# HackBoard.net
KiCad netlist of a schematic drawn in EAGLE
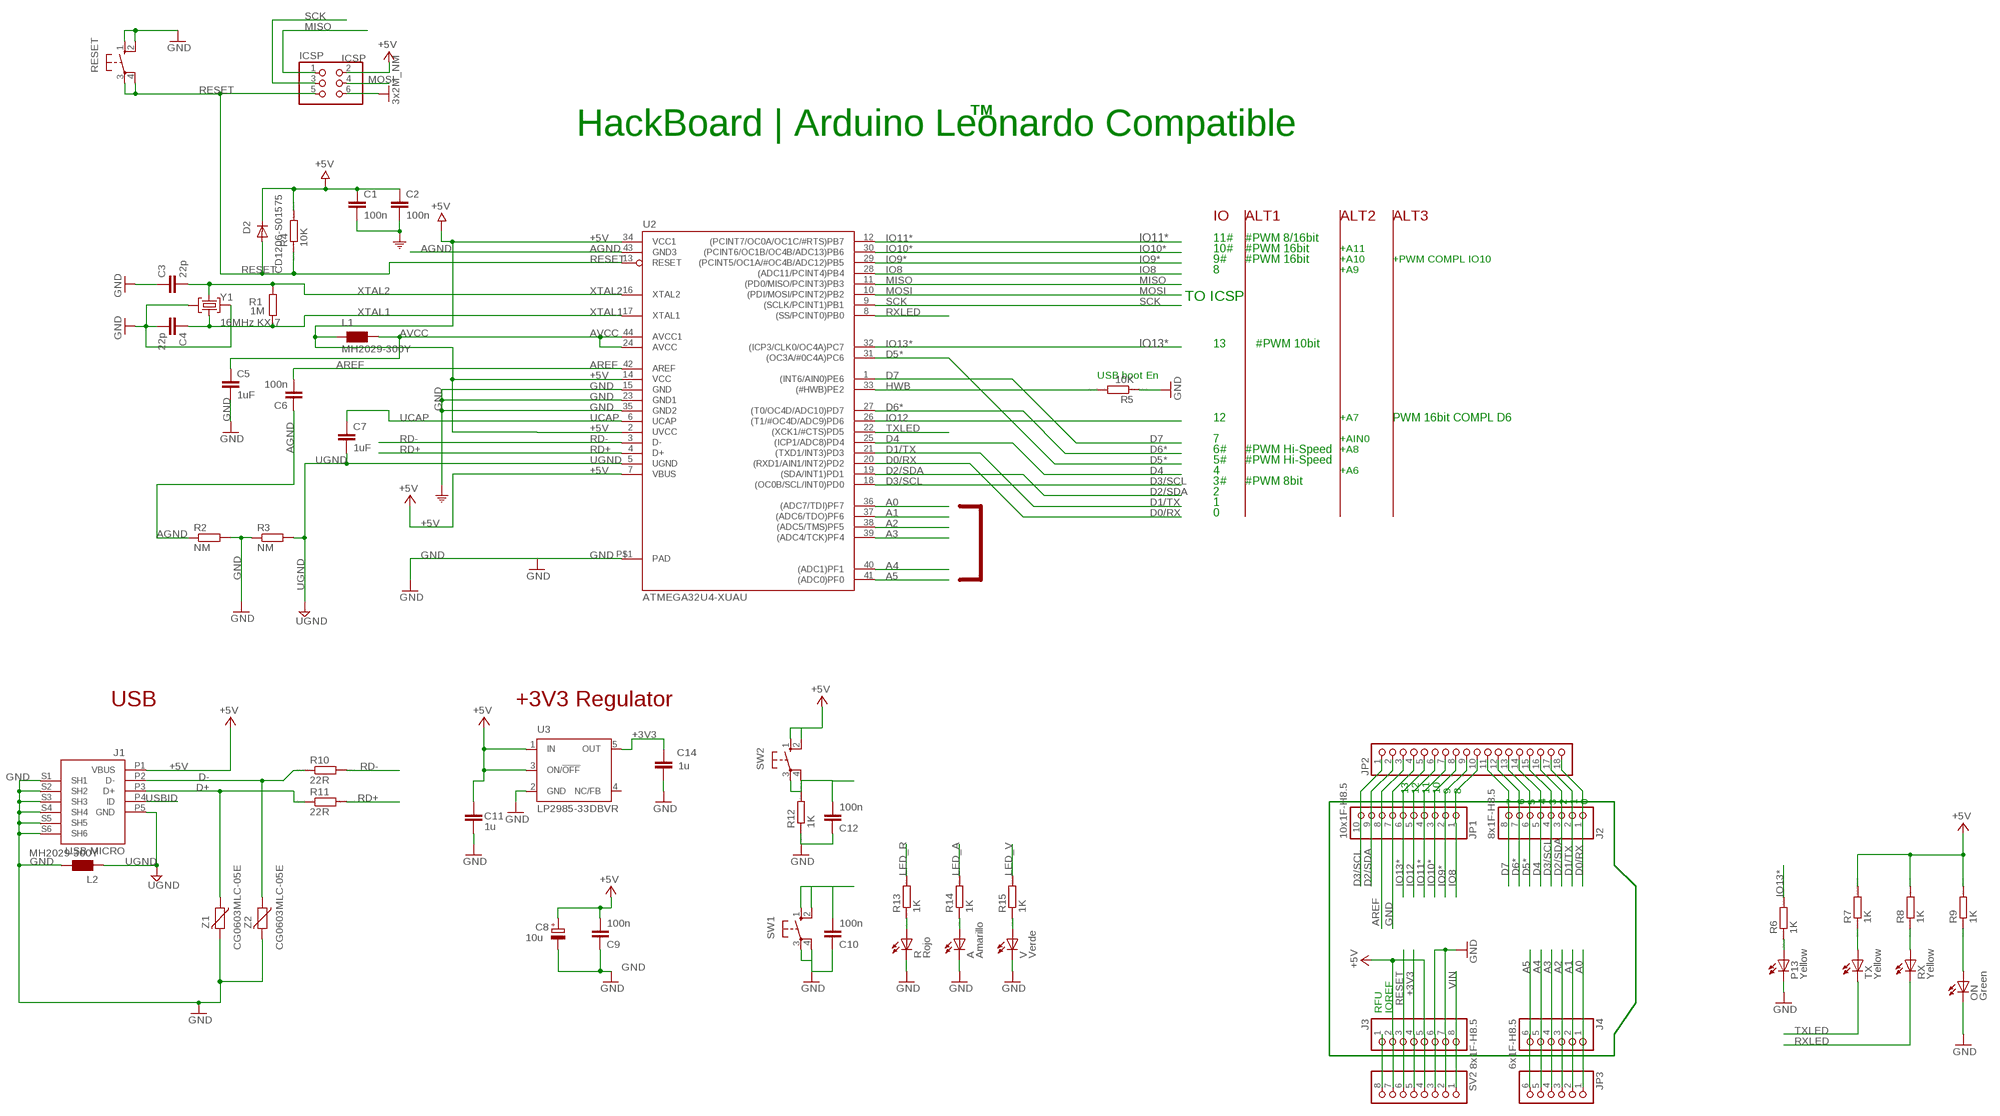
[diagram p0: schematic, sheet 1]

(export (version "E")
  (design (tool "Eeschema 10.0.6"))
  (components
    (comp (ref "A")
      (value "Amarillo")
      (footprint "eagle-import:CHIPLED_0805")
      (libsource (lib "eagle-import") (part "LEDCHIPLED_0805"))
    )
    (comp (ref "C1")
      (value "100n")
      (footprint "eagle-import:C0805")
      (libsource (lib "eagle-import") (part "rcl_C-EUC0805"))
    )
    (comp (ref "C2")
      (value "100n")
      (footprint "eagle-import:C0805")
      (libsource (lib "eagle-import") (part "rcl_C-EUC0805"))
    )
    (comp (ref "C3")
      (value "22p")
      (footprint "eagle-import:C0603-ROUND")
      (libsource (lib "eagle-import") (part "C-EUC0603"))
    )
    (comp (ref "C4")
      (value "22p")
      (footprint "eagle-import:C0603-ROUND")
      (libsource (lib "eagle-import") (part "C-EUC0603"))
    )
    (comp (ref "C5")
      (value "1uF")
      (footprint "eagle-import:C0603-ROUND")
      (libsource (lib "eagle-import") (part "C-EUC0603"))
    )
    (comp (ref "C6")
      (value "100n")
      (footprint "eagle-import:C0805")
      (libsource (lib "eagle-import") (part "rcl_C-EUC0805"))
    )
    (comp (ref "C7")
      (value "1uF")
      (footprint "eagle-import:C0603-ROUND")
      (libsource (lib "eagle-import") (part "C-EUC0603"))
    )
    (comp (ref "C8")
      (value "10u")
      (footprint "eagle-import:SMC_B")
      (libsource (lib "eagle-import") (part "CPOL-EUSMCB"))
    )
    (comp (ref "C9")
      (value "100n")
      (footprint "eagle-import:C0805")
      (libsource (lib "eagle-import") (part "rcl_C-EUC0805"))
    )
    (comp (ref "C10")
      (value "100n")
      (footprint "eagle-import:C0805")
      (libsource (lib "eagle-import") (part "rcl_C-EUC0805"))
    )
    (comp (ref "C11")
      (value "1u")
      (footprint "eagle-import:C0603-ROUND")
      (libsource (lib "eagle-import") (part "C-EUC0603"))
    )
    (comp (ref "C12")
      (value "100n")
      (footprint "eagle-import:C0805")
      (libsource (lib "eagle-import") (part "rcl_C-EUC0805"))
    )
    (comp (ref "C14")
      (value "1u")
      (footprint "eagle-import:C0603-ROUND")
      (libsource (lib "eagle-import") (part "C-EUC0603"))
    )
    (comp (ref "D2")
      (value "CD1206-S01575")
      (footprint "eagle-import:MINIMELF")
      (libsource (lib "eagle-import") (part "DIODE-MINIMELF"))
    )
    (comp (ref "ICSP")
      (value "ICSP")
      (footprint "eagle-import:2X03")
      (libsource (lib "eagle-import") (part "PINHD-2X3"))
    )
    (comp (ref "J1")
      (value "USB MICRO")
      (footprint "eagle-import:CON2_USB_MICRO_B_AT")
      (libsource (lib "eagle-import") (part "MYCON2_USB-MINI-B"))
    )
    (comp (ref "J2")
      (value "8x1F-H8.5")
      (footprint "eagle-import:1X08")
      (libsource (lib "eagle-import") (part "PINHD-1X8"))
    )
    (comp (ref "J3")
      (value "8x1F-H8.5")
      (footprint "eagle-import:1X08")
      (libsource (lib "eagle-import") (part "PINHD-1X8"))
    )
    (comp (ref "J4")
      (value "6x1F-H8.5")
      (footprint "eagle-import:1X06")
      (libsource (lib "eagle-import") (part "PINHD-1X6"))
    )
    (comp (ref "JP1")
      (value "10x1F-H8.5")
      (footprint "eagle-import:1X10")
      (libsource (lib "eagle-import") (part "PINHD-1X10"))
    )
    (comp (ref "JP2")
      (value "PINHD-1X18")
      (footprint "eagle-import:1X18")
      (libsource (lib "eagle-import") (part "PINHD-1X18"))
    )
    (comp (ref "JP3")
      (value "PINHD-1X6")
      (footprint "eagle-import:1X06")
      (libsource (lib "eagle-import") (part "pinhead_PINHD-1X6"))
    )
    (comp (ref "L1")
      (value "MH2029-300Y")
      (footprint "eagle-import:0805")
      (libsource (lib "eagle-import") (part "WE-CBF_0805"))
    )
    (comp (ref "L2")
      (value "MH2029-300Y")
      (footprint "eagle-import:0805")
      (libsource (lib "eagle-import") (part "WE-CBF_0805"))
    )
    (comp (ref "ON")
      (value "Green")
      (footprint "eagle-import:CHIPLED_0805")
      (libsource (lib "eagle-import") (part "LEDCHIPLED_0805"))
    )
    (comp (ref "P13")
      (value "Yellow")
      (footprint "eagle-import:CHIPLED_0805")
      (libsource (lib "eagle-import") (part "LEDCHIPLED_0805"))
    )
    (comp (ref "R")
      (value "Rojo")
      (footprint "eagle-import:CHIPLED_0805")
      (libsource (lib "eagle-import") (part "LEDCHIPLED_0805"))
    )
    (comp (ref "R1")
      (value "1M")
      (footprint "eagle-import:R0603-ROUND")
      (libsource (lib "eagle-import") (part "R-EU_R0603"))
    )
    (comp (ref "R2")
      (value "NM")
      (footprint "eagle-import:R0402")
      (libsource (lib "eagle-import") (part "R-EU_R0402"))
    )
    (comp (ref "R3")
      (value "NM")
      (footprint "eagle-import:R0402")
      (libsource (lib "eagle-import") (part "R-EU_R0402"))
    )
    (comp (ref "R4")
      (value "10K")
      (footprint "eagle-import:R0805")
      (libsource (lib "eagle-import") (part "R"))
    )
    (comp (ref "R5")
      (value "10K")
      (footprint "eagle-import:R0805")
      (libsource (lib "eagle-import") (part "R"))
    )
    (comp (ref "R6")
      (value "1K")
      (footprint "eagle-import:M0805")
      (libsource (lib "eagle-import") (part "resistor_R-EU_M0805"))
    )
    (comp (ref "R7")
      (value "1K")
      (footprint "eagle-import:M0805")
      (libsource (lib "eagle-import") (part "resistor_R-EU_M0805"))
    )
    (comp (ref "R8")
      (value "1K")
      (footprint "eagle-import:M0805")
      (libsource (lib "eagle-import") (part "resistor_R-EU_M0805"))
    )
    (comp (ref "R9")
      (value "1K")
      (footprint "eagle-import:M0805")
      (libsource (lib "eagle-import") (part "resistor_R-EU_M0805"))
    )
    (comp (ref "R10")
      (value "22R")
      (footprint "eagle-import:M0805")
      (libsource (lib "eagle-import") (part "resistor_R-EU_M0805"))
    )
    (comp (ref "R11")
      (value "22R")
      (footprint "eagle-import:M0805")
      (libsource (lib "eagle-import") (part "resistor_R-EU_M0805"))
    )
    (comp (ref "R12")
      (value "1K")
      (footprint "eagle-import:M0805")
      (libsource (lib "eagle-import") (part "resistor_R-EU_M0805"))
    )
    (comp (ref "R13")
      (value "1K")
      (footprint "eagle-import:M0805")
      (libsource (lib "eagle-import") (part "resistor_R-EU_M0805"))
    )
    (comp (ref "R14")
      (value "1K")
      (footprint "eagle-import:M0805")
      (libsource (lib "eagle-import") (part "resistor_R-EU_M0805"))
    )
    (comp (ref "R15")
      (value "1K")
      (footprint "eagle-import:M0805")
      (libsource (lib "eagle-import") (part "resistor_R-EU_M0805"))
    )
    (comp (ref "RESET")
      (value "10-XX")
      (footprint "eagle-import:B3F-10XX")
      (fields (field (name "MPN") "B3F-1000"))
      (libsource (lib "eagle-import") (part "10-XX"))
    )
    (comp (ref "RX")
      (value "Yellow")
      (footprint "eagle-import:CHIPLED_0805")
      (libsource (lib "eagle-import") (part "LEDCHIPLED_0805"))
    )
    (comp (ref "SV2")
      (value "PINHD-1X8")
      (footprint "eagle-import:1X08")
      (libsource (lib "eagle-import") (part "pinhead_PINHD-1X8"))
    )
    (comp (ref "SW1")
      (value "10-XX")
      (footprint "eagle-import:B3F-10XX")
      (fields (field (name "MPN") "B3F-1000"))
      (libsource (lib "eagle-import") (part "10-XX"))
    )
    (comp (ref "SW2")
      (value "10-XX")
      (footprint "eagle-import:B3F-10XX")
      (fields (field (name "MPN") "B3F-1000"))
      (libsource (lib "eagle-import") (part "10-XX"))
    )
    (comp (ref "TX")
      (value "Yellow")
      (footprint "eagle-import:CHIPLED_0805")
      (libsource (lib "eagle-import") (part "LEDCHIPLED_0805"))
    )
    (comp (ref "U2")
      (value "ATMEGA32U4-XUAU")
      (footprint "eagle-import:TQFP44-PAD")
      (libsource (lib "eagle-import") (part "ATMEGA32U4-XUAU"))
    )
    (comp (ref "U3")
      (value "LP2985-33DBVR")
      (footprint "eagle-import:SOT23-DBV")
      (libsource (lib "eagle-import") (part "LP2985-XXDBVR33"))
    )
    (comp (ref "V")
      (value "Verde")
      (footprint "eagle-import:CHIPLED_0805")
      (libsource (lib "eagle-import") (part "LEDCHIPLED_0805"))
    )
    (comp (ref "Y1")
      (value "16MHz KX-7")
      (footprint "eagle-import:CRYSTAL-3.2-2.5")
      (libsource (lib "eagle-import") (part "CRYSTAL-3.2-2.5"))
    )
    (comp (ref "Z1")
      (value "CG0603MLC-05E")
      (footprint "eagle-import:CT_CN0603")
      (libsource (lib "eagle-import") (part "VARISTORCN0603"))
    )
    (comp (ref "Z2")
      (value "CG0603MLC-05E")
      (footprint "eagle-import:CT_CN0603")
      (libsource (lib "eagle-import") (part "VARISTORCN0603"))
    )
  )
  (nets
    (net (code "1") (name "+5V") (class "Default")
      (node (ref "C1") (pin "1") (pinfunction "1_1") (pintype "passive"))
      (node (ref "C11") (pin "2") (pinfunction "2_2") (pintype "passive"))
      (node (ref "C2") (pin "1") (pinfunction "1_1") (pintype "passive"))
      (node (ref "C8") (pin "+") (pinfunction "+_+") (pintype "passive"))
      (node (ref "C9") (pin "2") (pinfunction "2_2") (pintype "passive"))
      (node (ref "D2") (pin "C") (pinfunction "C_C") (pintype "passive"))
      (node (ref "ICSP") (pin "2") (pinfunction "2_2") (pintype "passive"))
      (node (ref "J1") (pin "P1") (pinfunction "VBUS_P1") (pintype "power_in"))
      (node (ref "J3") (pin "2") (pinfunction "2_2") (pintype "passive"))
      (node (ref "J3") (pin "5") (pinfunction "5_5") (pintype "passive"))
      (node (ref "L1") (pin "1") (pinfunction "1_1") (pintype "passive"))
      (node (ref "R4") (pin "2") (pinfunction "2_2") (pintype "passive"))
      (node (ref "R7") (pin "2") (pinfunction "2_2") (pintype "passive"))
      (node (ref "R8") (pin "2") (pinfunction "2_2") (pintype "passive"))
      (node (ref "R9") (pin "2") (pinfunction "2_2") (pintype "passive"))
      (node (ref "SV2") (pin "4") (pinfunction "4_4") (pintype "passive"))
      (node (ref "SV2") (pin "7") (pinfunction "7_7") (pintype "passive"))
      (node (ref "SW2") (pin "1") (pinfunction "S_1") (pintype "passive"))
      (node (ref "SW2") (pin "2") (pinfunction "S1_2") (pintype "passive"))
      (node (ref "U2") (pin "14") (pinfunction "VCC_14") (pintype "power_in"))
      (node (ref "U2") (pin "2") (pinfunction "UVCC_2") (pintype "power_in"))
      (node (ref "U2") (pin "34") (pinfunction "VCC1_34") (pintype "power_in"))
      (node (ref "U2") (pin "7") (pinfunction "VBUS_7") (pintype "input"))
      (node (ref "U3") (pin "1") (pinfunction "IN_1") (pintype "input"))
      (node (ref "U3") (pin "3") (pinfunction "ON/~{OFF}_3") (pintype "input"))
    )
    (net (code "2") (name "/+3V3") (class "Default")
      (node (ref "C14") (pin "2") (pinfunction "2_2") (pintype "passive"))
      (node (ref "J3") (pin "4") (pinfunction "4_4") (pintype "passive"))
      (node (ref "SV2") (pin "5") (pinfunction "5_5") (pintype "passive"))
      (node (ref "U3") (pin "5") (pinfunction "OUT_5") (pintype "passive"))
    )
    (net (code "3") (name "/A0") (class "Default")
      (node (ref "J4") (pin "1") (pinfunction "1_1") (pintype "passive"))
      (node (ref "JP3") (pin "1") (pinfunction "1_1") (pintype "passive"))
      (node (ref "U2") (pin "36") (pinfunction "(ADC7/TDI)PF7_36") (pintype "bidirectional"))
    )
    (net (code "4") (name "/A1") (class "Default")
      (node (ref "J4") (pin "2") (pinfunction "2_2") (pintype "passive"))
      (node (ref "JP3") (pin "2") (pinfunction "2_2") (pintype "passive"))
      (node (ref "U2") (pin "37") (pinfunction "(ADC6/TDO)PF6_37") (pintype "bidirectional"))
    )
    (net (code "5") (name "/A2") (class "Default")
      (node (ref "J4") (pin "3") (pinfunction "3_3") (pintype "passive"))
      (node (ref "JP3") (pin "3") (pinfunction "3_3") (pintype "passive"))
      (node (ref "U2") (pin "38") (pinfunction "(ADC5/TMS)PF5_38") (pintype "bidirectional"))
    )
    (net (code "6") (name "/A3") (class "Default")
      (node (ref "J4") (pin "4") (pinfunction "4_4") (pintype "passive"))
      (node (ref "JP3") (pin "4") (pinfunction "4_4") (pintype "passive"))
      (node (ref "U2") (pin "39") (pinfunction "(ADC4/TCK)PF4_39") (pintype "bidirectional"))
    )
    (net (code "7") (name "/A4") (class "Default")
      (node (ref "J4") (pin "5") (pinfunction "5_5") (pintype "passive"))
      (node (ref "JP3") (pin "5") (pinfunction "5_5") (pintype "passive"))
      (node (ref "U2") (pin "40") (pinfunction "(ADC1)PF1_40") (pintype "bidirectional"))
    )
    (net (code "8") (name "/A5") (class "Default")
      (node (ref "J4") (pin "6") (pinfunction "6_6") (pintype "passive"))
      (node (ref "JP3") (pin "6") (pinfunction "6_6") (pintype "passive"))
      (node (ref "U2") (pin "41") (pinfunction "(ADC0)PF0_41") (pintype "bidirectional"))
    )
    (net (code "9") (name "/AGND") (class "Default")
      (node (ref "C6") (pin "1") (pinfunction "1_1") (pintype "passive"))
      (node (ref "R2") (pin "1") (pinfunction "1_1") (pintype "passive"))
      (node (ref "U2") (pin "43") (pinfunction "GND3_43") (pintype "power_in"))
    )
    (net (code "10") (name "/AREF") (class "Default")
      (node (ref "C6") (pin "2") (pinfunction "2_2") (pintype "passive"))
      (node (ref "JP1") (pin "8") (pinfunction "8_8") (pintype "passive"))
      (node (ref "JP2") (pin "3") (pinfunction "3_3") (pintype "passive"))
      (node (ref "U2") (pin "42") (pinfunction "AREF_42") (pintype "power_in"))
    )
    (net (code "11") (name "/AVCC") (class "Default")
      (node (ref "C5") (pin "1") (pinfunction "1_1") (pintype "passive"))
      (node (ref "L1") (pin "2") (pinfunction "2_2") (pintype "passive"))
      (node (ref "U2") (pin "24") (pinfunction "AVCC_24") (pintype "power_in"))
      (node (ref "U2") (pin "44") (pinfunction "AVCC1_44") (pintype "power_in"))
    )
    (net (code "12") (name "/D+") (class "Default")
      (node (ref "J1") (pin "P3") (pinfunction "D+_P3") (pintype "bidirectional"))
      (node (ref "R11") (pin "1") (pinfunction "1_1") (pintype "passive"))
      (node (ref "Z1") (pin "1") (pinfunction "1_1") (pintype "passive"))
    )
    (net (code "13") (name "/D-") (class "Default")
      (node (ref "J1") (pin "P2") (pinfunction "D-_P2") (pintype "bidirectional"))
      (node (ref "R10") (pin "1") (pinfunction "1_1") (pintype "passive"))
      (node (ref "Z2") (pin "1") (pinfunction "1_1") (pintype "passive"))
    )
    (net (code "14") (name "/D0{slash}RX") (class "Default")
      (node (ref "J2") (pin "1") (pinfunction "1_1") (pintype "passive"))
      (node (ref "JP2") (pin "18") (pinfunction "18_18") (pintype "passive"))
      (node (ref "U2") (pin "20") (pinfunction "(RXD1/AIN1/INT2)PD2_20") (pintype "bidirectional"))
    )
    (net (code "15") (name "/D1{slash}TX") (class "Default")
      (node (ref "J2") (pin "2") (pinfunction "2_2") (pintype "passive"))
      (node (ref "JP2") (pin "17") (pinfunction "17_17") (pintype "passive"))
      (node (ref "U2") (pin "21") (pinfunction "(TXD1/INT3)PD3_21") (pintype "bidirectional"))
    )
    (net (code "16") (name "/D2{slash}SDA") (class "Default")
      (node (ref "J2") (pin "3") (pinfunction "3_3") (pintype "passive"))
      (node (ref "JP1") (pin "9") (pinfunction "9_9") (pintype "passive"))
      (node (ref "JP2") (pin "16") (pinfunction "16_16") (pintype "passive"))
      (node (ref "JP2") (pin "2") (pinfunction "2_2") (pintype "passive"))
      (node (ref "U2") (pin "19") (pinfunction "(SDA/INT1)PD1_19") (pintype "bidirectional"))
    )
    (net (code "17") (name "/D3{slash}SCL") (class "Default")
      (node (ref "J2") (pin "4") (pinfunction "4_4") (pintype "passive"))
      (node (ref "JP1") (pin "10") (pinfunction "10_10") (pintype "passive"))
      (node (ref "JP2") (pin "1") (pinfunction "1_1") (pintype "passive"))
      (node (ref "JP2") (pin "15") (pinfunction "15_15") (pintype "passive"))
      (node (ref "U2") (pin "18") (pinfunction "(OC0B/SCL/INT0)PD0_18") (pintype "bidirectional"))
    )
    (net (code "18") (name "/D4") (class "Default")
      (node (ref "J2") (pin "5") (pinfunction "5_5") (pintype "passive"))
      (node (ref "JP2") (pin "14") (pinfunction "14_14") (pintype "passive"))
      (node (ref "U2") (pin "25") (pinfunction "(ICP1/ADC8)PD4_25") (pintype "bidirectional"))
    )
    (net (code "19") (name "/D5*") (class "Default")
      (node (ref "J2") (pin "6") (pinfunction "6_6") (pintype "passive"))
      (node (ref "JP2") (pin "13") (pinfunction "13_13") (pintype "passive"))
      (node (ref "U2") (pin "31") (pinfunction "(OC3A/#0C4A)PC6_31") (pintype "bidirectional"))
    )
    (net (code "20") (name "/D6*") (class "Default")
      (node (ref "J2") (pin "7") (pinfunction "7_7") (pintype "passive"))
      (node (ref "JP2") (pin "12") (pinfunction "12_12") (pintype "passive"))
      (node (ref "U2") (pin "27") (pinfunction "(T0/OC4D/ADC10)PD7_27") (pintype "bidirectional"))
    )
    (net (code "21") (name "/D7") (class "Default")
      (node (ref "J2") (pin "8") (pinfunction "8_8") (pintype "passive"))
      (node (ref "JP2") (pin "11") (pinfunction "11_11") (pintype "passive"))
      (node (ref "U2") (pin "1") (pinfunction "(INT6/AIN0)PE6_1") (pintype "bidirectional"))
    )
    (net (code "22") (name "/HWB") (class "Default")
      (node (ref "R5") (pin "2") (pinfunction "2_2") (pintype "passive"))
      (node (ref "U2") (pin "33") (pinfunction "(#HWB)PE2_33") (pintype "bidirectional"))
    )
    (net (code "23") (name "/IO8") (class "Default")
      (node (ref "JP1") (pin "1") (pinfunction "1_1") (pintype "passive"))
      (node (ref "JP2") (pin "10") (pinfunction "10_10") (pintype "passive"))
      (node (ref "U2") (pin "28") (pinfunction "(ADC11/PCINT4)PB4_28") (pintype "bidirectional"))
    )
    (net (code "24") (name "/IO9*") (class "Default")
      (node (ref "JP1") (pin "2") (pinfunction "2_2") (pintype "passive"))
      (node (ref "JP2") (pin "9") (pinfunction "9_9") (pintype "passive"))
      (node (ref "U2") (pin "29") (pinfunction "(PCINT5/OC1A/#OC4B/ADC12)PB5_29") (pintype "bidirectional"))
    )
    (net (code "25") (name "/IO10*") (class "Default")
      (node (ref "JP1") (pin "3") (pinfunction "3_3") (pintype "passive"))
      (node (ref "JP2") (pin "8") (pinfunction "8_8") (pintype "passive"))
      (node (ref "U2") (pin "30") (pinfunction "(PCINT6/OC1B/OC4B/ADC13)PB6_30") (pintype "bidirectional"))
    )
    (net (code "26") (name "/IO11*") (class "Default")
      (node (ref "JP1") (pin "4") (pinfunction "4_4") (pintype "passive"))
      (node (ref "JP2") (pin "7") (pinfunction "7_7") (pintype "passive"))
      (node (ref "U2") (pin "12") (pinfunction "(PCINT7/OC0A/OC1C/#RTS)PB7_12") (pintype "bidirectional"))
    )
    (net (code "27") (name "/IO12") (class "Default")
      (node (ref "JP1") (pin "5") (pinfunction "5_5") (pintype "passive"))
      (node (ref "JP2") (pin "6") (pinfunction "6_6") (pintype "passive"))
      (node (ref "U2") (pin "26") (pinfunction "(T1/#OC4D/ADC9)PD6_26") (pintype "bidirectional"))
    )
    (net (code "28") (name "/IO13*") (class "Default")
      (node (ref "JP1") (pin "6") (pinfunction "6_6") (pintype "passive"))
      (node (ref "JP2") (pin "5") (pinfunction "5_5") (pintype "passive"))
      (node (ref "R6") (pin "2") (pinfunction "2_2") (pintype "passive"))
      (node (ref "U2") (pin "32") (pinfunction "(ICP3/CLK0/OC4A)PC7_32") (pintype "bidirectional"))
    )
    (net (code "29") (name "/LED_A") (class "Default")
      (node (ref "R14") (pin "2") (pinfunction "2_2") (pintype "passive"))
    )
    (net (code "30") (name "/LED_R") (class "Default")
      (node (ref "R13") (pin "2") (pinfunction "2_2") (pintype "passive"))
    )
    (net (code "31") (name "/LED_V") (class "Default")
      (node (ref "R15") (pin "2") (pinfunction "2_2") (pintype "passive"))
    )
    (net (code "32") (name "/MISO") (class "Default")
      (node (ref "ICSP") (pin "1") (pinfunction "1_1") (pintype "passive"))
      (node (ref "U2") (pin "11") (pinfunction "(PD0/MISO/PCINT3)PB3_11") (pintype "bidirectional"))
    )
    (net (code "33") (name "/MOSI") (class "Default")
      (node (ref "ICSP") (pin "4") (pinfunction "4_4") (pintype "passive"))
      (node (ref "U2") (pin "10") (pinfunction "(PDI/MOSI/PCINT2)PB2_10") (pintype "bidirectional"))
    )
    (net (code "34") (name "/RD+") (class "Default")
      (node (ref "R11") (pin "2") (pinfunction "2_2") (pintype "passive"))
      (node (ref "U2") (pin "4") (pinfunction "D+_4") (pintype "bidirectional"))
    )
    (net (code "35") (name "/RD-") (class "Default")
      (node (ref "R10") (pin "2") (pinfunction "2_2") (pintype "passive"))
      (node (ref "U2") (pin "3") (pinfunction "D-_3") (pintype "bidirectional"))
    )
    (net (code "36") (name "/RESET") (class "Default")
      (node (ref "D2") (pin "A") (pinfunction "A_A") (pintype "passive"))
      (node (ref "ICSP") (pin "5") (pinfunction "5_5") (pintype "passive"))
      (node (ref "J3") (pin "3") (pinfunction "3_3") (pintype "passive"))
      (node (ref "R4") (pin "1") (pinfunction "1_1") (pintype "passive"))
      (node (ref "RESET") (pin "3") (pinfunction "P_3") (pintype "passive"))
      (node (ref "RESET") (pin "4") (pinfunction "P1_4") (pintype "passive"))
      (node (ref "SV2") (pin "6") (pinfunction "6_6") (pintype "passive"))
      (node (ref "U2") (pin "13") (pinfunction "RESET_13") (pintype "input"))
    )
    (net (code "37") (name "/RXLED") (class "Default")
      (node (ref "RX") (pin "C") (pinfunction "C_C") (pintype "passive"))
      (node (ref "U2") (pin "8") (pinfunction "(SS/PCINT0)PB0_8") (pintype "bidirectional"))
    )
    (net (code "38") (name "/SCK") (class "Default")
      (node (ref "ICSP") (pin "3") (pinfunction "3_3") (pintype "passive"))
      (node (ref "U2") (pin "9") (pinfunction "(SCLK/PCINT1)PB1_9") (pintype "bidirectional"))
    )
    (net (code "39") (name "/TXLED") (class "Default")
      (node (ref "TX") (pin "C") (pinfunction "C_C") (pintype "passive"))
      (node (ref "U2") (pin "22") (pinfunction "(XCK1/#CTS)PD5_22") (pintype "bidirectional"))
    )
    (net (code "40") (name "/UCAP") (class "Default")
      (node (ref "C7") (pin "1") (pinfunction "1_1") (pintype "passive"))
      (node (ref "U2") (pin "6") (pinfunction "UCAP_6") (pintype "passive"))
    )
    (net (code "41") (name "/USBID") (class "Default")
      (node (ref "J1") (pin "P4") (pinfunction "ID_P4") (pintype "bidirectional"))
    )
    (net (code "42") (name "/VIN") (class "Default")
      (node (ref "J3") (pin "8") (pinfunction "8_8") (pintype "passive"))
      (node (ref "SV2") (pin "1") (pinfunction "1_1") (pintype "passive"))
    )
    (net (code "43") (name "/XTAL1") (class "Default")
      (node (ref "C4") (pin "1") (pinfunction "1_1") (pintype "passive"))
      (node (ref "R1") (pin "1") (pinfunction "1_1") (pintype "passive"))
      (node (ref "U2") (pin "17") (pinfunction "XTAL1_17") (pintype "bidirectional"))
      (node (ref "Y1") (pin "1") (pinfunction "C1_1") (pintype "passive"))
    )
    (net (code "44") (name "/XTAL2") (class "Default")
      (node (ref "C3") (pin "2") (pinfunction "2_2") (pintype "passive"))
      (node (ref "R1") (pin "2") (pinfunction "2_2") (pintype "passive"))
      (node (ref "U2") (pin "16") (pinfunction "XTAL2_16") (pintype "bidirectional"))
      (node (ref "Y1") (pin "3") (pinfunction "C2_3") (pintype "passive"))
    )
    (net (code "45") (name "3x2M_NM") (class "Default")
      (node (ref "A") (pin "C") (pinfunction "C_C") (pintype "passive"))
      (node (ref "C1") (pin "2") (pinfunction "2_2") (pintype "passive"))
      (node (ref "C10") (pin "1") (pinfunction "1_1") (pintype "passive"))
      (node (ref "C11") (pin "1") (pinfunction "1_1") (pintype "passive"))
      (node (ref "C12") (pin "1") (pinfunction "1_1") (pintype "passive"))
      (node (ref "C14") (pin "1") (pinfunction "1_1") (pintype "passive"))
      (node (ref "C2") (pin "2") (pinfunction "2_2") (pintype "passive"))
      (node (ref "C3") (pin "1") (pinfunction "1_1") (pintype "passive"))
      (node (ref "C4") (pin "2") (pinfunction "2_2") (pintype "passive"))
      (node (ref "C5") (pin "2") (pinfunction "2_2") (pintype "passive"))
      (node (ref "C8") (pin "-") (pinfunction "-_-") (pintype "passive"))
      (node (ref "C9") (pin "1") (pinfunction "1_1") (pintype "passive"))
      (node (ref "ICSP") (pin "6") (pinfunction "6_6") (pintype "passive"))
      (node (ref "J1") (pin "S1") (pinfunction "SH1_S1") (pintype "passive"))
      (node (ref "J1") (pin "S2") (pinfunction "SH2_S2") (pintype "passive"))
      (node (ref "J1") (pin "S3") (pinfunction "SH3_S3") (pintype "passive"))
      (node (ref "J1") (pin "S4") (pinfunction "SH4_S4") (pintype "passive"))
      (node (ref "J1") (pin "S5") (pinfunction "SH5_S5") (pintype "passive"))
      (node (ref "J1") (pin "S6") (pinfunction "SH6_S6") (pintype "passive"))
      (node (ref "J3") (pin "6") (pinfunction "6_6") (pintype "passive"))
      (node (ref "J3") (pin "7") (pinfunction "7_7") (pintype "passive"))
      (node (ref "JP1") (pin "7") (pinfunction "7_7") (pintype "passive"))
      (node (ref "JP2") (pin "4") (pinfunction "4_4") (pintype "passive"))
      (node (ref "L2") (pin "2") (pinfunction "2_2") (pintype "passive"))
      (node (ref "ON") (pin "C") (pinfunction "C_C") (pintype "passive"))
      (node (ref "P13") (pin "C") (pinfunction "C_C") (pintype "passive"))
      (node (ref "R") (pin "C") (pinfunction "C_C") (pintype "passive"))
      (node (ref "R12") (pin "1") (pinfunction "1_1") (pintype "passive"))
      (node (ref "R2") (pin "2") (pinfunction "2_2") (pintype "passive"))
      (node (ref "R3") (pin "1") (pinfunction "1_1") (pintype "passive"))
      (node (ref "R5") (pin "1") (pinfunction "1_1") (pintype "passive"))
      (node (ref "RESET") (pin "1") (pinfunction "S_1") (pintype "passive"))
      (node (ref "RESET") (pin "2") (pinfunction "S1_2") (pintype "passive"))
      (node (ref "SV2") (pin "2") (pinfunction "2_2") (pintype "passive"))
      (node (ref "SV2") (pin "3") (pinfunction "3_3") (pintype "passive"))
      (node (ref "SW1") (pin "3") (pinfunction "P_3") (pintype "passive"))
      (node (ref "SW1") (pin "4") (pinfunction "P1_4") (pintype "passive"))
      (node (ref "U2") (pin "15") (pinfunction "GND_15") (pintype "power_in"))
      (node (ref "U2") (pin "23") (pinfunction "GND1_23") (pintype "power_in"))
      (node (ref "U2") (pin "35") (pinfunction "GND2_35") (pintype "power_in"))
      (node (ref "U2") (pin "P$1") (pinfunction "PAD_P$1") (pintype "power_in"))
      (node (ref "U3") (pin "2") (pinfunction "GND_2") (pintype "power_in"))
      (node (ref "V") (pin "C") (pinfunction "C_C") (pintype "passive"))
      (node (ref "Y1") (pin "2") (pinfunction "GND_2") (pintype "passive"))
      (node (ref "Y1") (pin "4") (pinfunction "GND_4") (pintype "passive"))
      (node (ref "Z1") (pin "2") (pinfunction "2_2") (pintype "passive"))
      (node (ref "Z2") (pin "2") (pinfunction "2_2") (pintype "passive"))
    )
    (net (code "46") (name "Net-(A-PadA)") (class "Default")
      (node (ref "A") (pin "A") (pinfunction "A_A") (pintype "passive"))
      (node (ref "R14") (pin "1") (pinfunction "1_1") (pintype "passive"))
    )
    (net (code "47") (name "Net-(J3-Pad1)") (class "Default")
      (node (ref "J3") (pin "1") (pinfunction "1_1") (pintype "passive"))
      (node (ref "SV2") (pin "8") (pinfunction "8_8") (pintype "passive"))
    )
    (net (code "48") (name "Net-(ON-PadA)") (class "Default")
      (node (ref "ON") (pin "A") (pinfunction "A_A") (pintype "passive"))
      (node (ref "R9") (pin "1") (pinfunction "1_1") (pintype "passive"))
    )
    (net (code "49") (name "Net-(P13-PadA)") (class "Default")
      (node (ref "P13") (pin "A") (pinfunction "A_A") (pintype "passive"))
      (node (ref "R6") (pin "1") (pinfunction "1_1") (pintype "passive"))
    )
    (net (code "50") (name "Net-(R-PadA)") (class "Default")
      (node (ref "R") (pin "A") (pinfunction "A_A") (pintype "passive"))
      (node (ref "R13") (pin "1") (pinfunction "1_1") (pintype "passive"))
    )
    (net (code "51") (name "Net-(R7-Pad1)") (class "Default")
      (node (ref "R7") (pin "1") (pinfunction "1_1") (pintype "passive"))
      (node (ref "TX") (pin "A") (pinfunction "A_A") (pintype "passive"))
    )
    (net (code "52") (name "Net-(R8-Pad1)") (class "Default")
      (node (ref "R8") (pin "1") (pinfunction "1_1") (pintype "passive"))
      (node (ref "RX") (pin "A") (pinfunction "A_A") (pintype "passive"))
    )
    (net (code "53") (name "Net-(R15-Pad1)") (class "Default")
      (node (ref "R15") (pin "1") (pinfunction "1_1") (pintype "passive"))
      (node (ref "V") (pin "A") (pinfunction "A_A") (pintype "passive"))
    )
    (net (code "54") (name "Net-(SW1-S)") (class "Default")
      (node (ref "C10") (pin "2") (pinfunction "2_2") (pintype "passive"))
      (node (ref "SW1") (pin "1") (pinfunction "S_1") (pintype "passive"))
      (node (ref "SW1") (pin "2") (pinfunction "S1_2") (pintype "passive"))
    )
    (net (code "55") (name "Net-(SW2-P)") (class "Default")
      (node (ref "C12") (pin "2") (pinfunction "2_2") (pintype "passive"))
      (node (ref "R12") (pin "2") (pinfunction "2_2") (pintype "passive"))
      (node (ref "SW2") (pin "3") (pinfunction "P_3") (pintype "passive"))
      (node (ref "SW2") (pin "4") (pinfunction "P1_4") (pintype "passive"))
    )
    (net (code "56") (name "UGND") (class "Default")
      (node (ref "C7") (pin "2") (pinfunction "2_2") (pintype "passive"))
      (node (ref "J1") (pin "P5") (pinfunction "GND_P5") (pintype "passive"))
      (node (ref "L2") (pin "1") (pinfunction "1_1") (pintype "passive"))
      (node (ref "R3") (pin "2") (pinfunction "2_2") (pintype "passive"))
      (node (ref "U2") (pin "5") (pinfunction "UGND_5") (pintype "power_in"))
    )
    (net (code "57") (name "unconnected-(U3-NC{slash}FB-Pad4)") (class "Default")
      (node (ref "U3") (pin "4") (pinfunction "NC/FB_4") (pintype "passive"))
    )
  )
)
